# LVDS.net
KiCad netlist of a schematic drawn in Altium Designer
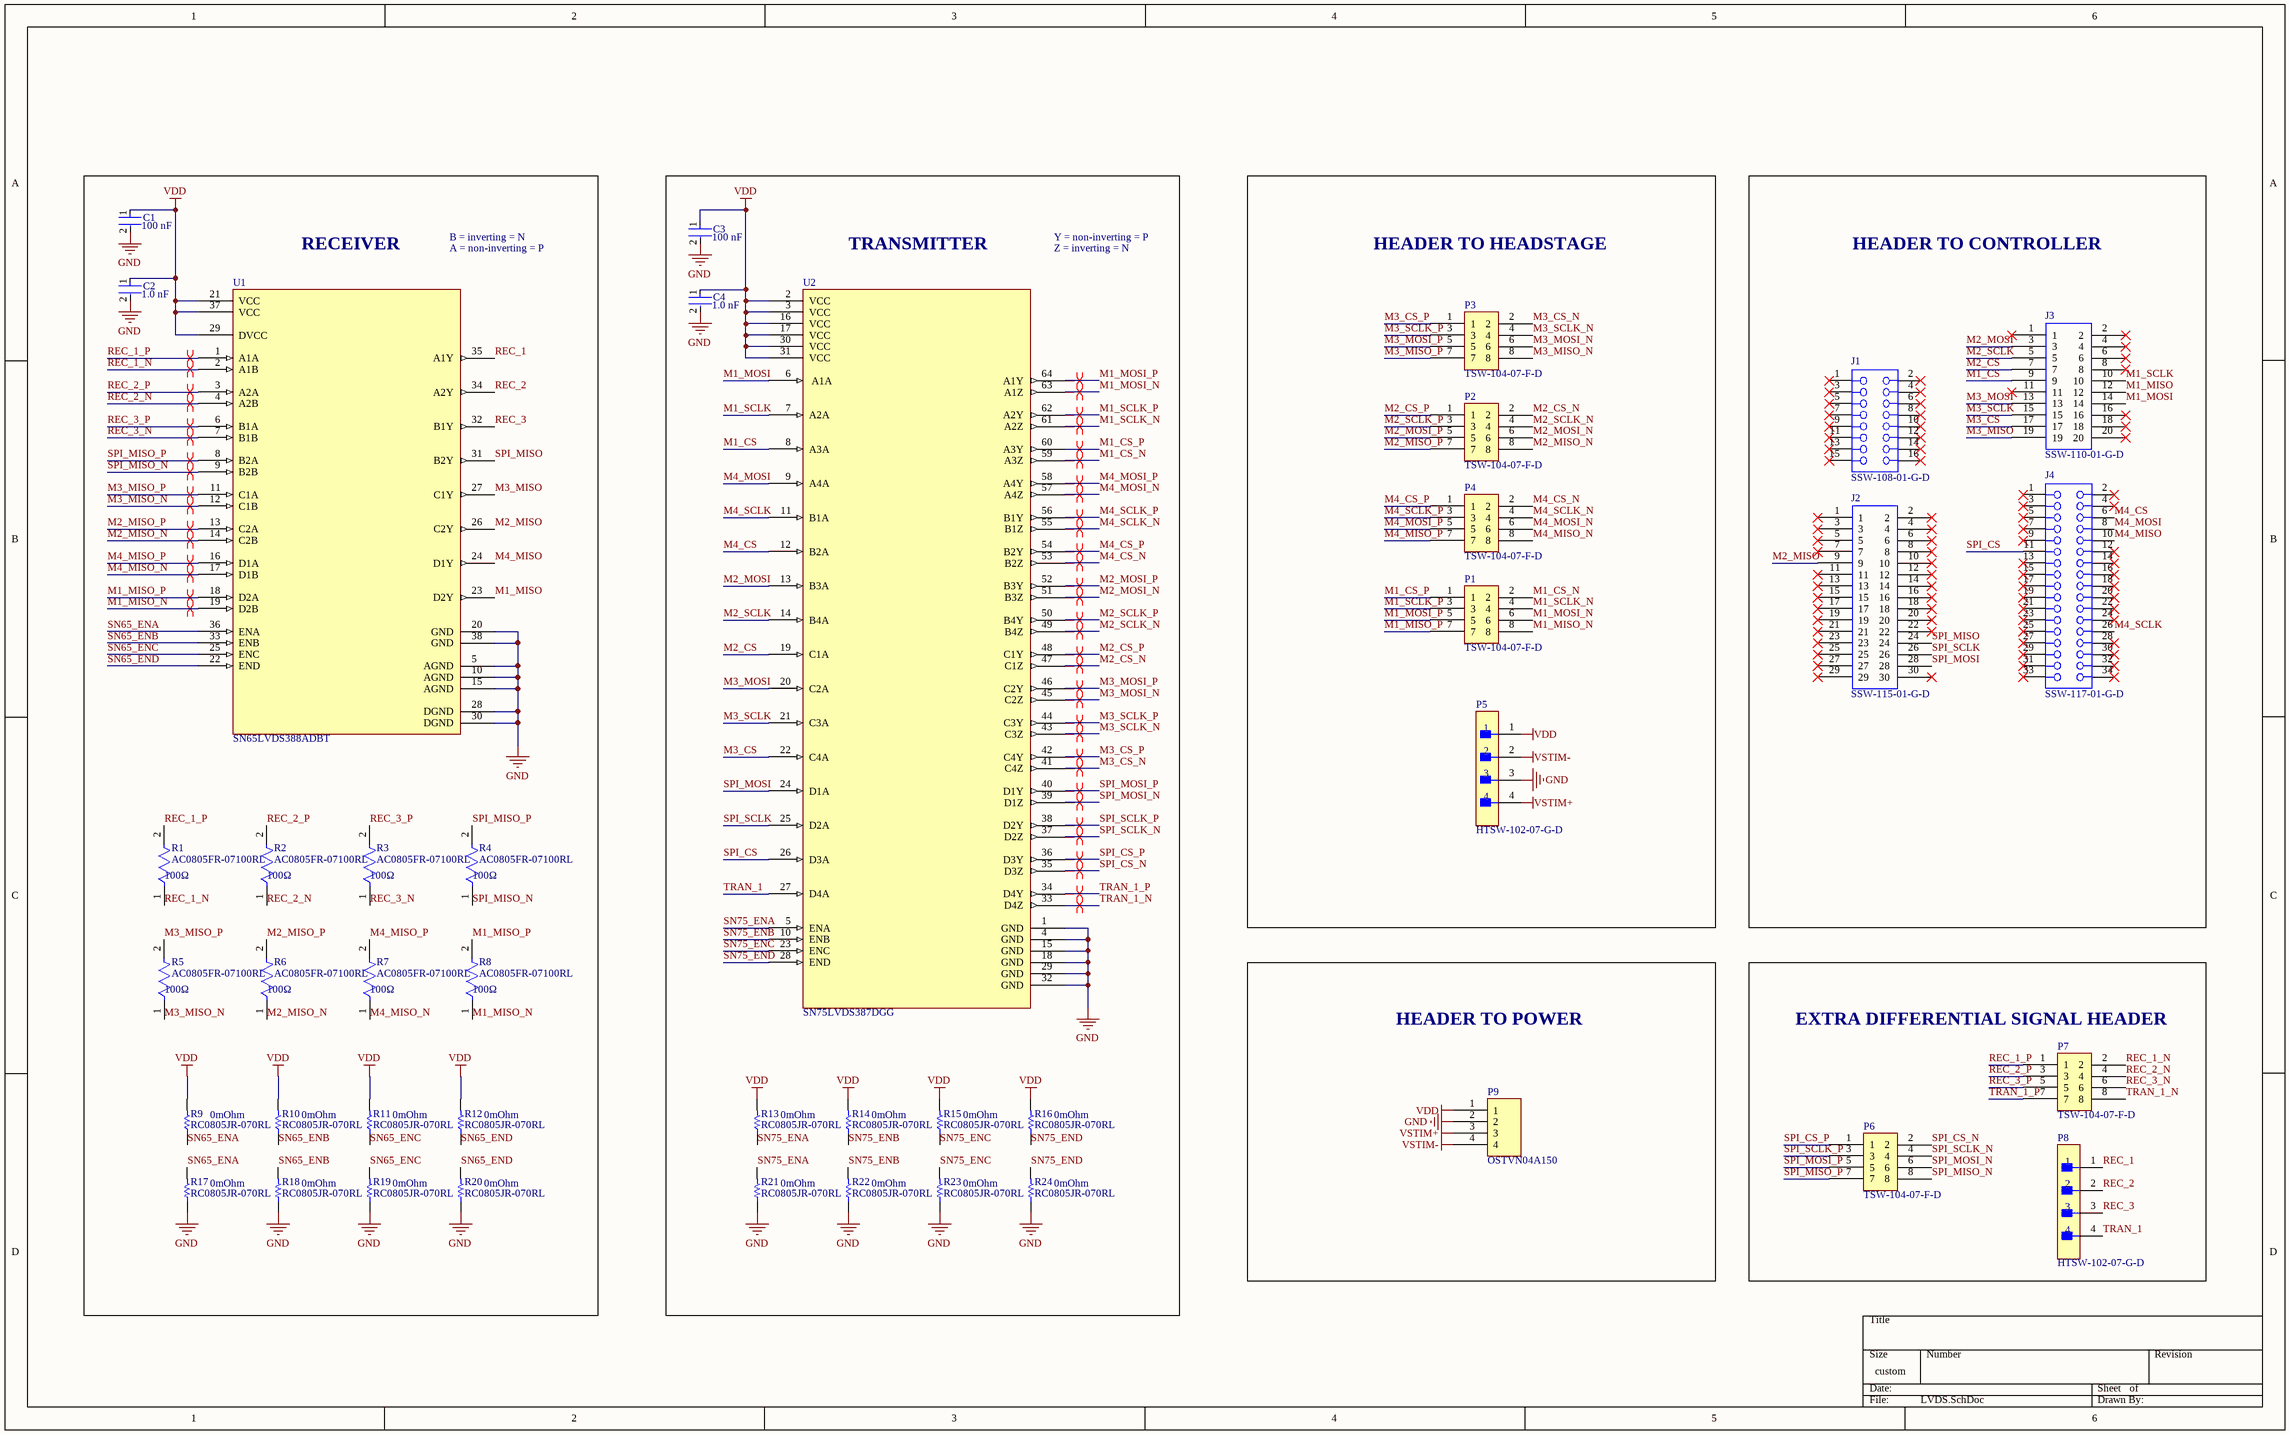
[diagram p0: LVDS.SchDoc]

(export (version "E")
  (design (tool "Eeschema 10.0.6"))
  (components
    (comp (ref "C1")
      (value "CC0805MRX7R9BB104")
      (footprint "FP-CC0805-0_85-MFG")
      (description "CAP CER 0.1UF 50V X7R 0805")
      (fields
        (field (name "TOLERANCE") "0.2")
        (field (name "OCTOPART") "https://octopart.com/cc0805mrx7r9bb104-yageo-30261726")
        (field (name "CAPACITANCE") "100 nF")
      )
      (libsource (lib "Altium Content Vault") (part "11868f565c42a9108669ba33697ecf6"))
    )
    (comp (ref "C2")
      (value "CC0805KRX7R9BB102")
      (footprint "FP-CC0805-0_85-MFG")
      (description "CAP CER 1000PF 50V X7R 0805")
      (fields
        (field (name "MANUFACTURER") "Yageo")
        (field (name "OCTOPART") "https://octopart.com/cc0805krx7r9bb102-yageo-39467744")
        (field (name "CAPACITANCE") "1.0 nF")
      )
      (libsource (lib "Altium Content Vault") (part "11868f565c42a9108669ba33697ecf6"))
    )
    (comp (ref "C3")
      (value "CC0805MRX7R9BB104")
      (footprint "FP-CC0805-0_85-MFG")
      (description "CAP CER 0.1UF 50V X7R 0805")
      (fields
        (field (name "TOLERANCE") "0.2")
        (field (name "OCTOPART") "https://octopart.com/cc0805mrx7r9bb104-yageo-30261726")
        (field (name "CAPACITANCE") "100 nF")
      )
      (libsource (lib "Altium Content Vault") (part "11868f565c42a9108669ba33697ecf6"))
    )
    (comp (ref "C4")
      (value "CC0805KRX7R9BB102")
      (footprint "FP-CC0805-0_85-MFG")
      (description "CAP CER 1000PF 50V X7R 0805")
      (fields
        (field (name "MANUFACTURER") "Yageo")
        (field (name "OCTOPART") "https://octopart.com/cc0805krx7r9bb102-yageo-39467744")
        (field (name "CAPACITANCE") "1.0 nF")
      )
      (libsource (lib "Altium Content Vault") (part "11868f565c42a9108669ba33697ecf6"))
    )
    (comp (ref "J1")
      (value "SSW-108-01-G-D")
      (footprint "SMTC-SSW-108-01-X-D")
      (description "SQ Post Socket, Through-hole, Vertical, -55 to 125 degC, 2.54mm Pitch, 16-Pin, Female, RoHS")
      (fields (field (name "MANUFACTURER") "Samtec"))
      (libsource (lib "Altium Content Vault") (part "SMTC-SSW-108-X-X-D-X"))
    )
    (comp (ref "J2")
      (value "SSW-115-01-G-D")
      (footprint "SAMTEC_SSW-115-01-G-D")
      (fields (field (name "MANUFACTURER") "Samtec"))
      (libsource (lib "LVDS") (part "SSW-115-01-G-D"))
    )
    (comp (ref "J3")
      (value "SSW-110-01-G-D")
      (footprint "SAMTEC_SSW-110-01-G-D")
      (fields (field (name "MANUFACTURER") "Samtec"))
      (libsource (lib "LVDS") (part "SSW-110-01-G-D"))
    )
    (comp (ref "J4")
      (value "SSW-117-01-G-D")
      (footprint "SMTC-SSW-117-01-X-D")
      (description "SQ Post Socket, Through-hole, Vertical, -55 to 125 degC, 2.54 mm Pitch, 34-Pin, Female, RoHS")
      (fields (field (name "MANUFACTURER") "Samtec"))
      (libsource (lib "Altium Content Vault") (part "SMTC-SSW-117-01-X-D"))
    )
    (comp (ref "P1")
      (value "TSW-104-07-F-D")
      (footprint "SAMTEC_TSW-104-07-F-D")
      (fields (field (name "MANUFACTURER") "Samtec"))
      (libsource (lib "LVDS") (part "TSW-104-07-F-D"))
    )
    (comp (ref "P2")
      (value "TSW-104-07-F-D")
      (footprint "SAMTEC_TSW-104-07-F-D")
      (fields (field (name "MANUFACTURER") "Samtec"))
      (libsource (lib "LVDS") (part "TSW-104-07-F-D"))
    )
    (comp (ref "P3")
      (value "TSW-104-07-F-D")
      (footprint "SAMTEC_TSW-104-07-F-D")
      (fields (field (name "MANUFACTURER") "Samtec"))
      (libsource (lib "LVDS") (part "TSW-104-07-F-D"))
    )
    (comp (ref "P4")
      (value "TSW-104-07-F-D")
      (footprint "SAMTEC_TSW-104-07-F-D")
      (fields (field (name "MANUFACTURER") "Samtec"))
      (libsource (lib "LVDS") (part "TSW-104-07-F-D"))
    )
    (comp (ref "P5")
      (value "HTSW-102-07-G-D")
      (footprint "FP-HTSW-102-07-G-D-MFG")
      (description "CONN HEADER VERT 4POS 2.54MM")
      (fields
        (field (name "MANUFACTURER") "Samtec")
        (field (name "OCTOPART") "https://octopart.com/htsw-102-07-g-d-samtec-10531767")
      )
      (libsource (lib "Altium Content Vault") (part "299a8cea1bdcbc3624fe62c390fa72c"))
    )
    (comp (ref "P6")
      (value "TSW-104-07-F-D")
      (footprint "SAMTEC_TSW-104-07-F-D")
      (fields (field (name "MANUFACTURER") "Samtec"))
      (libsource (lib "LVDS") (part "TSW-104-07-F-D"))
    )
    (comp (ref "P7")
      (value "TSW-104-07-F-D")
      (footprint "SAMTEC_TSW-104-07-F-D")
      (fields (field (name "MANUFACTURER") "Samtec"))
      (libsource (lib "LVDS") (part "TSW-104-07-F-D"))
    )
    (comp (ref "P8")
      (value "HTSW-102-07-G-D")
      (footprint "FP-HTSW-102-07-G-D-MFG")
      (description "CONN HEADER VERT 4POS 2.54MM")
      (fields
        (field (name "MANUFACTURER") "Samtec")
        (field (name "OCTOPART") "https://octopart.com/htsw-102-07-g-d-samtec-10531767")
      )
      (libsource (lib "Altium Content Vault") (part "299a8cea1bdcbc3624fe62c390fa72c"))
    )
    (comp (ref "P9")
      (value "OSTVN04A150")
      (footprint "OSTVN04A150")
      (description "Barrier Strip Terminal Block, 6A, 1 Row(s), 1 Deck(s)")
      (fields (field (name "MANUFACTURER") "On-Shore Technology") (field (name "SAFETY APPROVAL") "UL,CUL"))
      (libsource (lib "LVDS") (part "OSTVN04A150"))
    )
    (comp (ref "R1")
      (value "AC0805FR-07100RL")
      (footprint "FP-AC0805-MFG")
      (description "Res Thick Film 0805 100 Ohm 1% 1/8W ±100ppm/°C Molded SMD Paper T/R")
      (fields
        (field (name "TOLERANCE") "0.01")
        (field (name "OCTOPART") "https://octopart.com/ac0805fr-07100rl-yageo-24517276")
        (field (name "RESISTANCE") "100Ω")
      )
      (libsource (lib "Altium Content Vault") (part "1029c3af85768c4190bb7ad29bc67b5"))
    )
    (comp (ref "R2")
      (value "AC0805FR-07100RL")
      (footprint "FP-AC0805-MFG")
      (description "Res Thick Film 0805 100 Ohm 1% 1/8W ±100ppm/°C Molded SMD Paper T/R")
      (fields
        (field (name "TOLERANCE") "0.01")
        (field (name "OCTOPART") "https://octopart.com/ac0805fr-07100rl-yageo-24517276")
        (field (name "RESISTANCE") "100Ω")
      )
      (libsource (lib "Altium Content Vault") (part "1029c3af85768c4190bb7ad29bc67b5"))
    )
    (comp (ref "R3")
      (value "AC0805FR-07100RL")
      (footprint "FP-AC0805-MFG")
      (description "Res Thick Film 0805 100 Ohm 1% 1/8W ±100ppm/°C Molded SMD Paper T/R")
      (fields
        (field (name "TOLERANCE") "0.01")
        (field (name "OCTOPART") "https://octopart.com/ac0805fr-07100rl-yageo-24517276")
        (field (name "RESISTANCE") "100Ω")
      )
      (libsource (lib "Altium Content Vault") (part "1029c3af85768c4190bb7ad29bc67b5"))
    )
    (comp (ref "R4")
      (value "AC0805FR-07100RL")
      (footprint "FP-AC0805-MFG")
      (description "Res Thick Film 0805 100 Ohm 1% 1/8W ±100ppm/°C Molded SMD Paper T/R")
      (fields
        (field (name "TOLERANCE") "0.01")
        (field (name "OCTOPART") "https://octopart.com/ac0805fr-07100rl-yageo-24517276")
        (field (name "RESISTANCE") "100Ω")
      )
      (libsource (lib "Altium Content Vault") (part "1029c3af85768c4190bb7ad29bc67b5"))
    )
    (comp (ref "R5")
      (value "AC0805FR-07100RL")
      (footprint "FP-AC0805-MFG")
      (description "Res Thick Film 0805 100 Ohm 1% 1/8W ±100ppm/°C Molded SMD Paper T/R")
      (fields
        (field (name "TOLERANCE") "0.01")
        (field (name "OCTOPART") "https://octopart.com/ac0805fr-07100rl-yageo-24517276")
        (field (name "RESISTANCE") "100Ω")
      )
      (libsource (lib "Altium Content Vault") (part "1029c3af85768c4190bb7ad29bc67b5"))
    )
    (comp (ref "R6")
      (value "AC0805FR-07100RL")
      (footprint "FP-AC0805-MFG")
      (description "Res Thick Film 0805 100 Ohm 1% 1/8W ±100ppm/°C Molded SMD Paper T/R")
      (fields
        (field (name "TOLERANCE") "0.01")
        (field (name "OCTOPART") "https://octopart.com/ac0805fr-07100rl-yageo-24517276")
        (field (name "RESISTANCE") "100Ω")
      )
      (libsource (lib "Altium Content Vault") (part "1029c3af85768c4190bb7ad29bc67b5"))
    )
    (comp (ref "R7")
      (value "AC0805FR-07100RL")
      (footprint "FP-AC0805-MFG")
      (description "Res Thick Film 0805 100 Ohm 1% 1/8W ±100ppm/°C Molded SMD Paper T/R")
      (fields
        (field (name "TOLERANCE") "0.01")
        (field (name "OCTOPART") "https://octopart.com/ac0805fr-07100rl-yageo-24517276")
        (field (name "RESISTANCE") "100Ω")
      )
      (libsource (lib "Altium Content Vault") (part "1029c3af85768c4190bb7ad29bc67b5"))
    )
    (comp (ref "R8")
      (value "AC0805FR-07100RL")
      (footprint "FP-AC0805-MFG")
      (description "Res Thick Film 0805 100 Ohm 1% 1/8W ±100ppm/°C Molded SMD Paper T/R")
      (fields
        (field (name "TOLERANCE") "0.01")
        (field (name "OCTOPART") "https://octopart.com/ac0805fr-07100rl-yageo-24517276")
        (field (name "RESISTANCE") "100Ω")
      )
      (libsource (lib "Altium Content Vault") (part "1029c3af85768c4190bb7ad29bc67b5"))
    )
    (comp (ref "R9")
      (value "RC0805JR-070RL")
      (footprint "RESC2013X60X35ML10T20")
      (fields
        (field (name "RESISTANCE") "0mOhm")
        (field (name "TOLERANCE") "5%")
        (field (name "MANUFACTURER") "Yageo")
      )
      (libsource (lib "Altium Content Vault") (part "RES-2"))
    )
    (comp (ref "R10")
      (value "RC0805JR-070RL")
      (footprint "RESC2013X60X35ML10T20")
      (fields
        (field (name "RESISTANCE") "0mOhm")
        (field (name "TOLERANCE") "5%")
        (field (name "MANUFACTURER") "Yageo")
      )
      (libsource (lib "Altium Content Vault") (part "RES-2"))
    )
    (comp (ref "R11")
      (value "RC0805JR-070RL")
      (footprint "RESC2013X60X35ML10T20")
      (fields
        (field (name "RESISTANCE") "0mOhm")
        (field (name "TOLERANCE") "5%")
        (field (name "MANUFACTURER") "Yageo")
      )
      (libsource (lib "Altium Content Vault") (part "RES-2"))
    )
    (comp (ref "R12")
      (value "RC0805JR-070RL")
      (footprint "RESC2013X60X35ML10T20")
      (fields
        (field (name "RESISTANCE") "0mOhm")
        (field (name "TOLERANCE") "5%")
        (field (name "MANUFACTURER") "Yageo")
      )
      (libsource (lib "Altium Content Vault") (part "RES-2"))
    )
    (comp (ref "R13")
      (value "RC0805JR-070RL")
      (footprint "RESC2013X60X35ML10T20")
      (fields
        (field (name "RESISTANCE") "0mOhm")
        (field (name "TOLERANCE") "5%")
        (field (name "MANUFACTURER") "Yageo")
      )
      (libsource (lib "Altium Content Vault") (part "RES-2"))
    )
    (comp (ref "R14")
      (value "RC0805JR-070RL")
      (footprint "RESC2013X60X35ML10T20")
      (fields
        (field (name "RESISTANCE") "0mOhm")
        (field (name "TOLERANCE") "5%")
        (field (name "MANUFACTURER") "Yageo")
      )
      (libsource (lib "Altium Content Vault") (part "RES-2"))
    )
    (comp (ref "R15")
      (value "RC0805JR-070RL")
      (footprint "RESC2013X60X35ML10T20")
      (fields
        (field (name "RESISTANCE") "0mOhm")
        (field (name "TOLERANCE") "5%")
        (field (name "MANUFACTURER") "Yageo")
      )
      (libsource (lib "Altium Content Vault") (part "RES-2"))
    )
    (comp (ref "R16")
      (value "RC0805JR-070RL")
      (footprint "RESC2013X60X35ML10T20")
      (fields
        (field (name "RESISTANCE") "0mOhm")
        (field (name "TOLERANCE") "5%")
        (field (name "MANUFACTURER") "Yageo")
      )
      (libsource (lib "Altium Content Vault") (part "RES-2"))
    )
    (comp (ref "R17")
      (value "RC0805JR-070RL")
      (footprint "RESC2013X60X35ML10T20")
      (fields
        (field (name "RESISTANCE") "0mOhm")
        (field (name "TOLERANCE") "5%")
        (field (name "MANUFACTURER") "Yageo")
      )
      (libsource (lib "Altium Content Vault") (part "RES-2"))
    )
    (comp (ref "R18")
      (value "RC0805JR-070RL")
      (footprint "RESC2013X60X35ML10T20")
      (fields
        (field (name "RESISTANCE") "0mOhm")
        (field (name "TOLERANCE") "5%")
        (field (name "MANUFACTURER") "Yageo")
      )
      (libsource (lib "Altium Content Vault") (part "RES-2"))
    )
    (comp (ref "R19")
      (value "RC0805JR-070RL")
      (footprint "RESC2013X60X35ML10T20")
      (fields
        (field (name "RESISTANCE") "0mOhm")
        (field (name "TOLERANCE") "5%")
        (field (name "MANUFACTURER") "Yageo")
      )
      (libsource (lib "Altium Content Vault") (part "RES-2"))
    )
    (comp (ref "R20")
      (value "RC0805JR-070RL")
      (footprint "RESC2013X60X35ML10T20")
      (fields
        (field (name "RESISTANCE") "0mOhm")
        (field (name "TOLERANCE") "5%")
        (field (name "MANUFACTURER") "Yageo")
      )
      (libsource (lib "Altium Content Vault") (part "RES-2"))
    )
    (comp (ref "R21")
      (value "RC0805JR-070RL")
      (footprint "RESC2013X60X35ML10T20")
      (fields
        (field (name "RESISTANCE") "0mOhm")
        (field (name "TOLERANCE") "5%")
        (field (name "MANUFACTURER") "Yageo")
      )
      (libsource (lib "Altium Content Vault") (part "RES-2"))
    )
    (comp (ref "R22")
      (value "RC0805JR-070RL")
      (footprint "RESC2013X60X35ML10T20")
      (fields
        (field (name "RESISTANCE") "0mOhm")
        (field (name "TOLERANCE") "5%")
        (field (name "MANUFACTURER") "Yageo")
      )
      (libsource (lib "Altium Content Vault") (part "RES-2"))
    )
    (comp (ref "R23")
      (value "RC0805JR-070RL")
      (footprint "RESC2013X60X35ML10T20")
      (fields
        (field (name "RESISTANCE") "0mOhm")
        (field (name "TOLERANCE") "5%")
        (field (name "MANUFACTURER") "Yageo")
      )
      (libsource (lib "Altium Content Vault") (part "RES-2"))
    )
    (comp (ref "R24")
      (value "RC0805JR-070RL")
      (footprint "RESC2013X60X35ML10T20")
      (fields
        (field (name "RESISTANCE") "0mOhm")
        (field (name "TOLERANCE") "5%")
        (field (name "MANUFACTURER") "Yageo")
      )
      (libsource (lib "Altium Content Vault") (part "RES-2"))
    )
    (comp (ref "U1")
      (value "SN65LVDS388ADBT")
      (footprint "DBT0038A_N")
      (description "Line Receiver, 8 Func, 8 Rcvr, CMOS, PDSO38")
      (fields (field (name "MANUFACTURER") "Texas Instruments"))
      (libsource (lib "LVDS") (part "SN65LVDS388ADBT"))
    )
    (comp (ref "U2")
      (value "SN75LVDS387DGG")
      (footprint "DGG64")
      (description "Line Driver, 16 Func, 16 Driver, CMOS, PDSO64")
      (fields (field (name "MANUFACTURER") "Texas Instruments"))
      (libsource (lib "LVDS") (part "SN75LVDS387DGG"))
    )
  )
  (nets
    (net (code "1") (name "/M1_CS") (class "Default")
      (node (ref "J3") (pin "9") (pinfunction "9_9") (pintype "passive"))
      (node (ref "U2") (pin "8") (pinfunction "A3A_8") (pintype "input"))
    )
    (net (code "2") (name "/M1_CS_N") (class "Default")
      (node (ref "P1") (pin "2") (pinfunction "2_2") (pintype "passive"))
      (node (ref "U2") (pin "59") (pinfunction "A3Z_59") (pintype "output"))
    )
    (net (code "3") (name "/M1_CS_P") (class "Default")
      (node (ref "P1") (pin "1") (pinfunction "1_1") (pintype "passive"))
      (node (ref "U2") (pin "60") (pinfunction "A3Y_60") (pintype "output"))
    )
    (net (code "4") (name "/M1_MISO") (class "Default")
      (node (ref "J3") (pin "12") (pinfunction "12_12") (pintype "passive"))
      (node (ref "U1") (pin "23") (pinfunction "D2Y_23") (pintype "output"))
    )
    (net (code "5") (name "/M1_MISO_N") (class "Default")
      (node (ref "P1") (pin "8") (pinfunction "8_8") (pintype "passive"))
      (node (ref "R8") (pin "1") (pinfunction "1_1") (pintype "passive"))
      (node (ref "U1") (pin "19") (pinfunction "D2B_19") (pintype "input"))
    )
    (net (code "6") (name "/M1_MISO_P") (class "Default")
      (node (ref "P1") (pin "7") (pinfunction "7_7") (pintype "passive"))
      (node (ref "R8") (pin "2") (pinfunction "2_2") (pintype "passive"))
      (node (ref "U1") (pin "18") (pinfunction "D2A_18") (pintype "input"))
    )
    (net (code "7") (name "/M1_MOSI") (class "Default")
      (node (ref "J3") (pin "14") (pinfunction "14_14") (pintype "passive"))
      (node (ref "U2") (pin "6") (pinfunction "_A1A_6") (pintype "input"))
    )
    (net (code "8") (name "/M1_MOSI_N") (class "Default")
      (node (ref "P1") (pin "6") (pinfunction "6_6") (pintype "passive"))
      (node (ref "U2") (pin "63") (pinfunction "A1Z_63") (pintype "output"))
    )
    (net (code "9") (name "/M1_MOSI_P") (class "Default")
      (node (ref "P1") (pin "5") (pinfunction "5_5") (pintype "passive"))
      (node (ref "U2") (pin "64") (pinfunction "A1Y_64") (pintype "output"))
    )
    (net (code "10") (name "/M1_SCLK") (class "Default")
      (node (ref "J3") (pin "10") (pinfunction "10_10") (pintype "passive"))
      (node (ref "U2") (pin "7") (pinfunction "A2A_7") (pintype "input"))
    )
    (net (code "11") (name "/M1_SCLK_N") (class "Default")
      (node (ref "P1") (pin "4") (pinfunction "4_4") (pintype "passive"))
      (node (ref "U2") (pin "61") (pinfunction "A2Z_61") (pintype "output"))
    )
    (net (code "12") (name "/M1_SCLK_P") (class "Default")
      (node (ref "P1") (pin "3") (pinfunction "3_3") (pintype "passive"))
      (node (ref "U2") (pin "62") (pinfunction "A2Y_62") (pintype "output"))
    )
    (net (code "13") (name "/M2_CS") (class "Default")
      (node (ref "J3") (pin "7") (pinfunction "7_7") (pintype "passive"))
      (node (ref "U2") (pin "19") (pinfunction "C1A_19") (pintype "input"))
    )
    (net (code "14") (name "/M2_CS_N") (class "Default")
      (node (ref "P2") (pin "2") (pinfunction "2_2") (pintype "passive"))
      (node (ref "U2") (pin "47") (pinfunction "C1Z_47") (pintype "output"))
    )
    (net (code "15") (name "/M2_CS_P") (class "Default")
      (node (ref "P2") (pin "1") (pinfunction "1_1") (pintype "passive"))
      (node (ref "U2") (pin "48") (pinfunction "C1Y_48") (pintype "output"))
    )
    (net (code "16") (name "/M2_MISO") (class "Default")
      (node (ref "J2") (pin "9") (pinfunction "9_9") (pintype "passive"))
      (node (ref "U1") (pin "26") (pinfunction "C2Y_26") (pintype "output"))
    )
    (net (code "17") (name "/M2_MISO_N") (class "Default")
      (node (ref "P2") (pin "8") (pinfunction "8_8") (pintype "passive"))
      (node (ref "R6") (pin "1") (pinfunction "1_1") (pintype "passive"))
      (node (ref "U1") (pin "14") (pinfunction "C2B_14") (pintype "input"))
    )
    (net (code "18") (name "/M2_MISO_P") (class "Default")
      (node (ref "P2") (pin "7") (pinfunction "7_7") (pintype "passive"))
      (node (ref "R6") (pin "2") (pinfunction "2_2") (pintype "passive"))
      (node (ref "U1") (pin "13") (pinfunction "C2A_13") (pintype "input"))
    )
    (net (code "19") (name "/M2_MOSI") (class "Default")
      (node (ref "J3") (pin "3") (pinfunction "3_3") (pintype "passive"))
      (node (ref "U2") (pin "13") (pinfunction "B3A_13") (pintype "input"))
    )
    (net (code "20") (name "/M2_MOSI_N") (class "Default")
      (node (ref "P2") (pin "6") (pinfunction "6_6") (pintype "passive"))
      (node (ref "U2") (pin "51") (pinfunction "B3Z_51") (pintype "output"))
    )
    (net (code "21") (name "/M2_MOSI_P") (class "Default")
      (node (ref "P2") (pin "5") (pinfunction "5_5") (pintype "passive"))
      (node (ref "U2") (pin "52") (pinfunction "B3Y_52") (pintype "output"))
    )
    (net (code "22") (name "/M2_SCLK") (class "Default")
      (node (ref "J3") (pin "5") (pinfunction "5_5") (pintype "passive"))
      (node (ref "U2") (pin "14") (pinfunction "B4A_14") (pintype "input"))
    )
    (net (code "23") (name "/M2_SCLK_N") (class "Default")
      (node (ref "P2") (pin "4") (pinfunction "4_4") (pintype "passive"))
      (node (ref "U2") (pin "49") (pinfunction "B4Z_49") (pintype "output"))
    )
    (net (code "24") (name "/M2_SCLK_P") (class "Default")
      (node (ref "P2") (pin "3") (pinfunction "3_3") (pintype "passive"))
      (node (ref "U2") (pin "50") (pinfunction "B4Y_50") (pintype "output"))
    )
    (net (code "25") (name "/M3_CS") (class "Default")
      (node (ref "J3") (pin "17") (pinfunction "17_17") (pintype "passive"))
      (node (ref "U2") (pin "22") (pinfunction "C4A_22") (pintype "input"))
    )
    (net (code "26") (name "/M3_CS_N") (class "Default")
      (node (ref "P3") (pin "2") (pinfunction "2_2") (pintype "passive"))
      (node (ref "U2") (pin "41") (pinfunction "C4Z_41") (pintype "output"))
    )
    (net (code "27") (name "/M3_CS_P") (class "Default")
      (node (ref "P3") (pin "1") (pinfunction "1_1") (pintype "passive"))
      (node (ref "U2") (pin "42") (pinfunction "C4Y_42") (pintype "output"))
    )
    (net (code "28") (name "/M3_MISO") (class "Default")
      (node (ref "J3") (pin "19") (pinfunction "19_19") (pintype "passive"))
      (node (ref "U1") (pin "27") (pinfunction "C1Y_27") (pintype "output"))
    )
    (net (code "29") (name "/M3_MISO_N") (class "Default")
      (node (ref "P3") (pin "8") (pinfunction "8_8") (pintype "passive"))
      (node (ref "R5") (pin "1") (pinfunction "1_1") (pintype "passive"))
      (node (ref "U1") (pin "12") (pinfunction "C1B_12") (pintype "input"))
    )
    (net (code "30") (name "/M3_MISO_P") (class "Default")
      (node (ref "P3") (pin "7") (pinfunction "7_7") (pintype "passive"))
      (node (ref "R5") (pin "2") (pinfunction "2_2") (pintype "passive"))
      (node (ref "U1") (pin "11") (pinfunction "C1A_11") (pintype "input"))
    )
    (net (code "31") (name "/M3_MOSI") (class "Default")
      (node (ref "J3") (pin "13") (pinfunction "13_13") (pintype "passive"))
      (node (ref "U2") (pin "20") (pinfunction "C2A_20") (pintype "input"))
    )
    (net (code "32") (name "/M3_MOSI_N") (class "Default")
      (node (ref "P3") (pin "6") (pinfunction "6_6") (pintype "passive"))
      (node (ref "U2") (pin "45") (pinfunction "C2Z_45") (pintype "output"))
    )
    (net (code "33") (name "/M3_MOSI_P") (class "Default")
      (node (ref "P3") (pin "5") (pinfunction "5_5") (pintype "passive"))
      (node (ref "U2") (pin "46") (pinfunction "C2Y_46") (pintype "output"))
    )
    (net (code "34") (name "/M3_SCLK") (class "Default")
      (node (ref "J3") (pin "15") (pinfunction "15_15") (pintype "passive"))
      (node (ref "U2") (pin "21") (pinfunction "C3A_21") (pintype "input"))
    )
    (net (code "35") (name "/M3_SCLK_N") (class "Default")
      (node (ref "P3") (pin "4") (pinfunction "4_4") (pintype "passive"))
      (node (ref "U2") (pin "43") (pinfunction "C3Z_43") (pintype "output"))
    )
    (net (code "36") (name "/M3_SCLK_P") (class "Default")
      (node (ref "P3") (pin "3") (pinfunction "3_3") (pintype "passive"))
      (node (ref "U2") (pin "44") (pinfunction "C3Y_44") (pintype "output"))
    )
    (net (code "37") (name "/M4_CS") (class "Default")
      (node (ref "J4") (pin "6") (pinfunction "6_6") (pintype "passive"))
      (node (ref "U2") (pin "12") (pinfunction "B2A_12") (pintype "input"))
    )
    (net (code "38") (name "/M4_CS_N") (class "Default")
      (node (ref "P4") (pin "2") (pinfunction "2_2") (pintype "passive"))
      (node (ref "U2") (pin "53") (pinfunction "B2Z_53") (pintype "output"))
    )
    (net (code "39") (name "/M4_CS_P") (class "Default")
      (node (ref "P4") (pin "1") (pinfunction "1_1") (pintype "passive"))
      (node (ref "U2") (pin "54") (pinfunction "B2Y_54") (pintype "output"))
    )
    (net (code "40") (name "/M4_MISO") (class "Default")
      (node (ref "J4") (pin "10") (pinfunction "10_10") (pintype "passive"))
      (node (ref "U1") (pin "24") (pinfunction "D1Y_24") (pintype "output"))
    )
    (net (code "41") (name "/M4_MISO_N") (class "Default")
      (node (ref "P4") (pin "8") (pinfunction "8_8") (pintype "passive"))
      (node (ref "R7") (pin "1") (pinfunction "1_1") (pintype "passive"))
      (node (ref "U1") (pin "17") (pinfunction "D1B_17") (pintype "input"))
    )
    (net (code "42") (name "/M4_MISO_P") (class "Default")
      (node (ref "P4") (pin "7") (pinfunction "7_7") (pintype "passive"))
      (node (ref "R7") (pin "2") (pinfunction "2_2") (pintype "passive"))
      (node (ref "U1") (pin "16") (pinfunction "D1A_16") (pintype "input"))
    )
    (net (code "43") (name "/M4_MOSI") (class "Default")
      (node (ref "J4") (pin "8") (pinfunction "8_8") (pintype "passive"))
      (node (ref "U2") (pin "9") (pinfunction "A4A_9") (pintype "input"))
    )
    (net (code "44") (name "/M4_MOSI_N") (class "Default")
      (node (ref "P4") (pin "6") (pinfunction "6_6") (pintype "passive"))
      (node (ref "U2") (pin "57") (pinfunction "A4Z_57") (pintype "output"))
    )
    (net (code "45") (name "/M4_MOSI_P") (class "Default")
      (node (ref "P4") (pin "5") (pinfunction "5_5") (pintype "passive"))
      (node (ref "U2") (pin "58") (pinfunction "A4Y_58") (pintype "output"))
    )
    (net (code "46") (name "/M4_SCLK") (class "Default")
      (node (ref "J4") (pin "26") (pinfunction "26_26") (pintype "passive"))
      (node (ref "U2") (pin "11") (pinfunction "B1A_11") (pintype "input"))
    )
    (net (code "47") (name "/M4_SCLK_N") (class "Default")
      (node (ref "P4") (pin "4") (pinfunction "4_4") (pintype "passive"))
      (node (ref "U2") (pin "55") (pinfunction "B1Z_55") (pintype "output"))
    )
    (net (code "48") (name "/M4_SCLK_P") (class "Default")
      (node (ref "P4") (pin "3") (pinfunction "3_3") (pintype "passive"))
      (node (ref "U2") (pin "56") (pinfunction "B1Y_56") (pintype "output"))
    )
    (net (code "49") (name "/REC_1") (class "Default")
      (node (ref "P8") (pin "1") (pinfunction "1_1") (pintype "passive"))
      (node (ref "U1") (pin "35") (pinfunction "A1Y_35") (pintype "output"))
    )
    (net (code "50") (name "/REC_1_N") (class "Default")
      (node (ref "P7") (pin "2") (pinfunction "2_2") (pintype "passive"))
      (node (ref "R1") (pin "1") (pinfunction "1_1") (pintype "passive"))
      (node (ref "U1") (pin "2") (pinfunction "A1B_2") (pintype "input"))
    )
    (net (code "51") (name "/REC_1_P") (class "Default")
      (node (ref "P7") (pin "1") (pinfunction "1_1") (pintype "passive"))
      (node (ref "R1") (pin "2") (pinfunction "2_2") (pintype "passive"))
      (node (ref "U1") (pin "1") (pinfunction "A1A_1") (pintype "input"))
    )
    (net (code "52") (name "/REC_2") (class "Default")
      (node (ref "P8") (pin "2") (pinfunction "2_2") (pintype "passive"))
      (node (ref "U1") (pin "34") (pinfunction "A2Y_34") (pintype "output"))
    )
    (net (code "53") (name "/REC_2_N") (class "Default")
      (node (ref "P7") (pin "4") (pinfunction "4_4") (pintype "passive"))
      (node (ref "R2") (pin "1") (pinfunction "1_1") (pintype "passive"))
      (node (ref "U1") (pin "4") (pinfunction "A2B_4") (pintype "input"))
    )
    (net (code "54") (name "/REC_2_P") (class "Default")
      (node (ref "P7") (pin "3") (pinfunction "3_3") (pintype "passive"))
      (node (ref "R2") (pin "2") (pinfunction "2_2") (pintype "passive"))
      (node (ref "U1") (pin "3") (pinfunction "A2A_3") (pintype "input"))
    )
    (net (code "55") (name "/REC_3") (class "Default")
      (node (ref "P8") (pin "3") (pinfunction "3_3") (pintype "passive"))
      (node (ref "U1") (pin "32") (pinfunction "B1Y_32") (pintype "output"))
    )
    (net (code "56") (name "/REC_3_N") (class "Default")
      (node (ref "P7") (pin "6") (pinfunction "6_6") (pintype "passive"))
      (node (ref "R3") (pin "1") (pinfunction "1_1") (pintype "passive"))
      (node (ref "U1") (pin "7") (pinfunction "B1B_7") (pintype "input"))
    )
    (net (code "57") (name "/REC_3_P") (class "Default")
      (node (ref "P7") (pin "5") (pinfunction "5_5") (pintype "passive"))
      (node (ref "R3") (pin "2") (pinfunction "2_2") (pintype "passive"))
      (node (ref "U1") (pin "6") (pinfunction "B1A_6") (pintype "input"))
    )
    (net (code "58") (name "/SN65_ENA") (class "Default")
      (node (ref "R17") (pin "2") (pinfunction "2_2") (pintype "passive"))
      (node (ref "R9") (pin "1") (pinfunction "1_1") (pintype "passive"))
      (node (ref "U1") (pin "36") (pinfunction "ENA_36") (pintype "input"))
    )
    (net (code "59") (name "/SN65_ENB") (class "Default")
      (node (ref "R10") (pin "1") (pinfunction "1_1") (pintype "passive"))
      (node (ref "R18") (pin "2") (pinfunction "2_2") (pintype "passive"))
      (node (ref "U1") (pin "33") (pinfunction "ENB_33") (pintype "input"))
    )
    (net (code "60") (name "/SN65_ENC") (class "Default")
      (node (ref "R11") (pin "1") (pinfunction "1_1") (pintype "passive"))
      (node (ref "R19") (pin "2") (pinfunction "2_2") (pintype "passive"))
      (node (ref "U1") (pin "25") (pinfunction "ENC_25") (pintype "input"))
    )
    (net (code "61") (name "/SN65_END") (class "Default")
      (node (ref "R12") (pin "1") (pinfunction "1_1") (pintype "passive"))
      (node (ref "R20") (pin "2") (pinfunction "2_2") (pintype "passive"))
      (node (ref "U1") (pin "22") (pinfunction "END_22") (pintype "input"))
    )
    (net (code "62") (name "/SN75_ENA") (class "Default")
      (node (ref "R13") (pin "1") (pinfunction "1_1") (pintype "passive"))
      (node (ref "R21") (pin "2") (pinfunction "2_2") (pintype "passive"))
      (node (ref "U2") (pin "5") (pinfunction "ENA_5") (pintype "input"))
    )
    (net (code "63") (name "/SN75_ENB") (class "Default")
      (node (ref "R14") (pin "1") (pinfunction "1_1") (pintype "passive"))
      (node (ref "R22") (pin "2") (pinfunction "2_2") (pintype "passive"))
      (node (ref "U2") (pin "10") (pinfunction "ENB_10") (pintype "input"))
    )
    (net (code "64") (name "/SN75_ENC") (class "Default")
      (node (ref "R15") (pin "1") (pinfunction "1_1") (pintype "passive"))
      (node (ref "R23") (pin "2") (pinfunction "2_2") (pintype "passive"))
      (node (ref "U2") (pin "23") (pinfunction "ENC_23") (pintype "input"))
    )
    (net (code "65") (name "/SN75_END") (class "Default")
      (node (ref "R16") (pin "1") (pinfunction "1_1") (pintype "passive"))
      (node (ref "R24") (pin "2") (pinfunction "2_2") (pintype "passive"))
      (node (ref "U2") (pin "28") (pinfunction "END_28") (pintype "input"))
    )
    (net (code "66") (name "/SPI_CS") (class "Default")
      (node (ref "J4") (pin "11") (pinfunction "11_11") (pintype "passive"))
      (node (ref "U2") (pin "26") (pinfunction "D3A_26") (pintype "input"))
    )
    (net (code "67") (name "/SPI_CS_N") (class "Default")
      (node (ref "P6") (pin "2") (pinfunction "2_2") (pintype "passive"))
      (node (ref "U2") (pin "35") (pinfunction "D3Z_35") (pintype "output"))
    )
    (net (code "68") (name "/SPI_CS_P") (class "Default")
      (node (ref "P6") (pin "1") (pinfunction "1_1") (pintype "passive"))
      (node (ref "U2") (pin "36") (pinfunction "D3Y_36") (pintype "output"))
    )
    (net (code "69") (name "/SPI_MISO") (class "Default")
      (node (ref "J2") (pin "24") (pinfunction "24_24") (pintype "passive"))
      (node (ref "U1") (pin "31") (pinfunction "B2Y_31") (pintype "output"))
    )
    (net (code "70") (name "/SPI_MISO_N") (class "Default")
      (node (ref "P6") (pin "8") (pinfunction "8_8") (pintype "passive"))
      (node (ref "R4") (pin "1") (pinfunction "1_1") (pintype "passive"))
      (node (ref "U1") (pin "9") (pinfunction "B2B_9") (pintype "input"))
    )
    (net (code "71") (name "/SPI_MISO_P") (class "Default")
      (node (ref "P6") (pin "7") (pinfunction "7_7") (pintype "passive"))
      (node (ref "R4") (pin "2") (pinfunction "2_2") (pintype "passive"))
      (node (ref "U1") (pin "8") (pinfunction "B2A_8") (pintype "input"))
    )
    (net (code "72") (name "/SPI_MOSI") (class "Default")
      (node (ref "J2") (pin "28") (pinfunction "28_28") (pintype "passive"))
      (node (ref "U2") (pin "24") (pinfunction "D1A_24") (pintype "input"))
    )
    (net (code "73") (name "/SPI_MOSI_N") (class "Default")
      (node (ref "P6") (pin "6") (pinfunction "6_6") (pintype "passive"))
      (node (ref "U2") (pin "39") (pinfunction "D1Z_39") (pintype "output"))
    )
    (net (code "74") (name "/SPI_MOSI_P") (class "Default")
      (node (ref "P6") (pin "5") (pinfunction "5_5") (pintype "passive"))
      (node (ref "U2") (pin "40") (pinfunction "D1Y_40") (pintype "output"))
    )
    (net (code "75") (name "/SPI_SCLK") (class "Default")
      (node (ref "J2") (pin "26") (pinfunction "26_26") (pintype "passive"))
      (node (ref "U2") (pin "25") (pinfunction "D2A_25") (pintype "input"))
    )
    (net (code "76") (name "/SPI_SCLK_N") (class "Default")
      (node (ref "P6") (pin "4") (pinfunction "4_4") (pintype "passive"))
      (node (ref "U2") (pin "37") (pinfunction "D2Z_37") (pintype "output"))
    )
    (net (code "77") (name "/SPI_SCLK_P") (class "Default")
      (node (ref "P6") (pin "3") (pinfunction "3_3") (pintype "passive"))
      (node (ref "U2") (pin "38") (pinfunction "D2Y_38") (pintype "output"))
    )
    (net (code "78") (name "/TRAN_1") (class "Default")
      (node (ref "P8") (pin "4") (pinfunction "4_4") (pintype "passive"))
      (node (ref "U2") (pin "27") (pinfunction "D4A_27") (pintype "input"))
    )
    (net (code "79") (name "/TRAN_1_N") (class "Default")
      (node (ref "P7") (pin "8") (pinfunction "8_8") (pintype "passive"))
      (node (ref "U2") (pin "33") (pinfunction "D4Z_33") (pintype "output"))
    )
    (net (code "80") (name "/TRAN_1_P") (class "Default")
      (node (ref "P7") (pin "7") (pinfunction "7_7") (pintype "passive"))
      (node (ref "U2") (pin "34") (pinfunction "D4Y_34") (pintype "output"))
    )
    (net (code "81") (name "GND") (class "Default")
      (node (ref "C1") (pin "2") (pinfunction "2_2") (pintype "passive"))
      (node (ref "C2") (pin "2") (pinfunction "2_2") (pintype "passive"))
      (node (ref "C3") (pin "2") (pinfunction "2_2") (pintype "passive"))
      (node (ref "C4") (pin "2") (pinfunction "2_2") (pintype "passive"))
      (node (ref "P5") (pin "3") (pinfunction "3_3") (pintype "passive"))
      (node (ref "P9") (pin "2") (pinfunction "2_2") (pintype "passive"))
      (node (ref "R17") (pin "1") (pinfunction "1_1") (pintype "passive"))
      (node (ref "R18") (pin "1") (pinfunction "1_1") (pintype "passive"))
      (node (ref "R19") (pin "1") (pinfunction "1_1") (pintype "passive"))
      (node (ref "R20") (pin "1") (pinfunction "1_1") (pintype "passive"))
      (node (ref "R21") (pin "1") (pinfunction "1_1") (pintype "passive"))
      (node (ref "R22") (pin "1") (pinfunction "1_1") (pintype "passive"))
      (node (ref "R23") (pin "1") (pinfunction "1_1") (pintype "passive"))
      (node (ref "R24") (pin "1") (pinfunction "1_1") (pintype "passive"))
      (node (ref "U1") (pin "10") (pinfunction "AGND_10") (pintype "power_in"))
      (node (ref "U1") (pin "15") (pinfunction "AGND_15") (pintype "power_in"))
      (node (ref "U1") (pin "20") (pinfunction "GND_20") (pintype "power_in"))
      (node (ref "U1") (pin "28") (pinfunction "DGND_28") (pintype "power_in"))
      (node (ref "U1") (pin "30") (pinfunction "DGND_30") (pintype "power_in"))
      (node (ref "U1") (pin "38") (pinfunction "GND_38") (pintype "power_in"))
      (node (ref "U1") (pin "5") (pinfunction "AGND_5") (pintype "power_in"))
      (node (ref "U2") (pin "1") (pinfunction "GND_1") (pintype "power_in"))
      (node (ref "U2") (pin "15") (pinfunction "GND_15") (pintype "power_in"))
      (node (ref "U2") (pin "18") (pinfunction "GND_18") (pintype "power_in"))
      (node (ref "U2") (pin "29") (pinfunction "GND_29") (pintype "power_in"))
      (node (ref "U2") (pin "32") (pinfunction "GND_32") (pintype "power_in"))
      (node (ref "U2") (pin "4") (pinfunction "GND_4") (pintype "power_in"))
    )
    (net (code "82") (name "VDD") (class "Default")
      (node (ref "C1") (pin "1") (pinfunction "1_1") (pintype "passive"))
      (node (ref "C2") (pin "1") (pinfunction "1_1") (pintype "passive"))
      (node (ref "C3") (pin "1") (pinfunction "1_1") (pintype "passive"))
      (node (ref "C4") (pin "1") (pinfunction "1_1") (pintype "passive"))
      (node (ref "P5") (pin "1") (pinfunction "1_1") (pintype "passive"))
      (node (ref "P9") (pin "1") (pinfunction "1_1") (pintype "passive"))
      (node (ref "R10") (pin "2") (pinfunction "2_2") (pintype "passive"))
      (node (ref "R11") (pin "2") (pinfunction "2_2") (pintype "passive"))
      (node (ref "R12") (pin "2") (pinfunction "2_2") (pintype "passive"))
      (node (ref "R13") (pin "2") (pinfunction "2_2") (pintype "passive"))
      (node (ref "R14") (pin "2") (pinfunction "2_2") (pintype "passive"))
      (node (ref "R15") (pin "2") (pinfunction "2_2") (pintype "passive"))
      (node (ref "R16") (pin "2") (pinfunction "2_2") (pintype "passive"))
      (node (ref "R9") (pin "2") (pinfunction "2_2") (pintype "passive"))
      (node (ref "U1") (pin "21") (pinfunction "VCC_21") (pintype "power_in"))
      (node (ref "U1") (pin "29") (pinfunction "DVCC_29") (pintype "power_in"))
      (node (ref "U1") (pin "37") (pinfunction "VCC_37") (pintype "power_in"))
      (node (ref "U2") (pin "16") (pinfunction "VCC_16") (pintype "power_in"))
      (node (ref "U2") (pin "17") (pinfunction "VCC_17") (pintype "power_in"))
      (node (ref "U2") (pin "2") (pinfunction "VCC_2") (pintype "power_in"))
      (node (ref "U2") (pin "3") (pinfunction "VCC_3") (pintype "power_in"))
      (node (ref "U2") (pin "30") (pinfunction "VCC_30") (pintype "power_in"))
      (node (ref "U2") (pin "31") (pinfunction "VCC_31") (pintype "power_in"))
    )
    (net (code "83") (name "VSTIM+") (class "Default")
      (node (ref "P5") (pin "4") (pinfunction "4_4") (pintype "passive"))
      (node (ref "P9") (pin "3") (pinfunction "3_3") (pintype "passive"))
    )
    (net (code "84") (name "VSTIM-") (class "Default")
      (node (ref "P5") (pin "2") (pinfunction "2_2") (pintype "passive"))
      (node (ref "P9") (pin "4") (pinfunction "4_4") (pintype "passive"))
    )
    (net (code "85") (name "unconnected-(J1-Pad1)") (class "Default")
      (node (ref "J1") (pin "1") (pinfunction "1_1") (pintype "passive+no_connect"))
    )
    (net (code "86") (name "unconnected-(J1-Pad2)") (class "Default")
      (node (ref "J1") (pin "2") (pinfunction "2_2") (pintype "passive+no_connect"))
    )
    (net (code "87") (name "unconnected-(J1-Pad3)") (class "Default")
      (node (ref "J1") (pin "3") (pinfunction "3_3") (pintype "passive+no_connect"))
    )
    (net (code "88") (name "unconnected-(J1-Pad4)") (class "Default")
      (node (ref "J1") (pin "4") (pinfunction "4_4") (pintype "passive+no_connect"))
    )
    (net (code "89") (name "unconnected-(J1-Pad5)") (class "Default")
      (node (ref "J1") (pin "5") (pinfunction "5_5") (pintype "passive+no_connect"))
    )
    (net (code "90") (name "unconnected-(J1-Pad6)") (class "Default")
      (node (ref "J1") (pin "6") (pinfunction "6_6") (pintype "passive+no_connect"))
    )
    (net (code "91") (name "unconnected-(J1-Pad7)") (class "Default")
      (node (ref "J1") (pin "7") (pinfunction "7_7") (pintype "passive+no_connect"))
    )
    (net (code "92") (name "unconnected-(J1-Pad8)") (class "Default")
      (node (ref "J1") (pin "8") (pinfunction "8_8") (pintype "passive+no_connect"))
    )
    (net (code "93") (name "unconnected-(J1-Pad9)") (class "Default")
      (node (ref "J1") (pin "9") (pinfunction "9_9") (pintype "passive+no_connect"))
    )
    (net (code "94") (name "unconnected-(J1-Pad10)") (class "Default")
      (node (ref "J1") (pin "10") (pinfunction "10_10") (pintype "passive+no_connect"))
    )
    (net (code "95") (name "unconnected-(J1-Pad11)") (class "Default")
      (node (ref "J1") (pin "11") (pinfunction "11_11") (pintype "passive+no_connect"))
    )
    (net (code "96") (name "unconnected-(J1-Pad12)") (class "Default")
      (node (ref "J1") (pin "12") (pinfunction "12_12") (pintype "passive+no_connect"))
    )
    (net (code "97") (name "unconnected-(J1-Pad13)") (class "Default")
      (node (ref "J1") (pin "13") (pinfunction "13_13") (pintype "passive+no_connect"))
    )
    (net (code "98") (name "unconnected-(J1-Pad14)") (class "Default")
      (node (ref "J1") (pin "14") (pinfunction "14_14") (pintype "passive+no_connect"))
    )
    (net (code "99") (name "unconnected-(J1-Pad15)") (class "Default")
      (node (ref "J1") (pin "15") (pinfunction "15_15") (pintype "passive+no_connect"))
    )
    (net (code "100") (name "unconnected-(J1-Pad16)") (class "Default")
      (node (ref "J1") (pin "16") (pinfunction "16_16") (pintype "passive+no_connect"))
    )
    (net (code "101") (name "unconnected-(J2-Pad1)") (class "Default")
      (node (ref "J2") (pin "1") (pinfunction "1_1") (pintype "passive+no_connect"))
    )
    (net (code "102") (name "unconnected-(J2-Pad2)") (class "Default")
      (node (ref "J2") (pin "2") (pinfunction "2_2") (pintype "passive+no_connect"))
    )
    (net (code "103") (name "unconnected-(J2-Pad3)") (class "Default")
      (node (ref "J2") (pin "3") (pinfunction "3_3") (pintype "passive+no_connect"))
    )
    (net (code "104") (name "unconnected-(J2-Pad4)") (class "Default")
      (node (ref "J2") (pin "4") (pinfunction "4_4") (pintype "passive+no_connect"))
    )
    (net (code "105") (name "unconnected-(J2-Pad5)") (class "Default")
      (node (ref "J2") (pin "5") (pinfunction "5_5") (pintype "passive+no_connect"))
    )
    (net (code "106") (name "unconnected-(J2-Pad6)") (class "Default")
      (node (ref "J2") (pin "6") (pinfunction "6_6") (pintype "passive+no_connect"))
    )
    (net (code "107") (name "unconnected-(J2-Pad7)") (class "Default")
      (node (ref "J2") (pin "7") (pinfunction "7_7") (pintype "passive+no_connect"))
    )
    (net (code "108") (name "unconnected-(J2-Pad8)") (class "Default")
      (node (ref "J2") (pin "8") (pinfunction "8_8") (pintype "passive+no_connect"))
    )
    (net (code "109") (name "unconnected-(J2-Pad10)") (class "Default")
      (node (ref "J2") (pin "10") (pinfunction "10_10") (pintype "passive+no_connect"))
    )
    (net (code "110") (name "unconnected-(J2-Pad11)") (class "Default")
      (node (ref "J2") (pin "11") (pinfunction "11_11") (pintype "passive+no_connect"))
    )
    (net (code "111") (name "unconnected-(J2-Pad12)") (class "Default")
      (node (ref "J2") (pin "12") (pinfunction "12_12") (pintype "passive+no_connect"))
    )
    (net (code "112") (name "unconnected-(J2-Pad13)") (class "Default")
      (node (ref "J2") (pin "13") (pinfunction "13_13") (pintype "passive+no_connect"))
    )
    (net (code "113") (name "unconnected-(J2-Pad14)") (class "Default")
      (node (ref "J2") (pin "14") (pinfunction "14_14") (pintype "passive+no_connect"))
    )
    (net (code "114") (name "unconnected-(J2-Pad15)") (class "Default")
      (node (ref "J2") (pin "15") (pinfunction "15_15") (pintype "passive+no_connect"))
    )
    (net (code "115") (name "unconnected-(J2-Pad16)") (class "Default")
      (node (ref "J2") (pin "16") (pinfunction "16_16") (pintype "passive+no_connect"))
    )
    (net (code "116") (name "unconnected-(J2-Pad17)") (class "Default")
      (node (ref "J2") (pin "17") (pinfunction "17_17") (pintype "passive+no_connect"))
    )
    (net (code "117") (name "unconnected-(J2-Pad18)") (class "Default")
      (node (ref "J2") (pin "18") (pinfunction "18_18") (pintype "passive+no_connect"))
    )
    (net (code "118") (name "unconnected-(J2-Pad19)") (class "Default")
      (node (ref "J2") (pin "19") (pinfunction "19_19") (pintype "passive+no_connect"))
    )
    (net (code "119") (name "unconnected-(J2-Pad20)") (class "Default")
      (node (ref "J2") (pin "20") (pinfunction "20_20") (pintype "passive+no_connect"))
    )
    (net (code "120") (name "unconnected-(J2-Pad21)") (class "Default")
      (node (ref "J2") (pin "21") (pinfunction "21_21") (pintype "passive+no_connect"))
    )
    (net (code "121") (name "unconnected-(J2-Pad22)") (class "Default")
      (node (ref "J2") (pin "22") (pinfunction "22_22") (pintype "passive+no_connect"))
    )
    (net (code "122") (name "unconnected-(J2-Pad23)") (class "Default")
      (node (ref "J2") (pin "23") (pinfunction "23_23") (pintype "passive+no_connect"))
    )
    (net (code "123") (name "unconnected-(J2-Pad25)") (class "Default")
      (node (ref "J2") (pin "25") (pinfunction "25_25") (pintype "passive+no_connect"))
    )
    (net (code "124") (name "unconnected-(J2-Pad27)") (class "Default")
      (node (ref "J2") (pin "27") (pinfunction "27_27") (pintype "passive+no_connect"))
    )
    (net (code "125") (name "unconnected-(J2-Pad29)") (class "Default")
      (node (ref "J2") (pin "29") (pinfunction "29_29") (pintype "passive+no_connect"))
    )
    (net (code "126") (name "unconnected-(J2-Pad30)") (class "Default")
      (node (ref "J2") (pin "30") (pinfunction "30_30") (pintype "passive+no_connect"))
    )
    (net (code "127") (name "unconnected-(J3-Pad1)") (class "Default")
      (node (ref "J3") (pin "1") (pinfunction "1_1") (pintype "passive+no_connect"))
    )
    (net (code "128") (name "unconnected-(J3-Pad2)") (class "Default")
      (node (ref "J3") (pin "2") (pinfunction "2_2") (pintype "passive+no_connect"))
    )
    (net (code "129") (name "unconnected-(J3-Pad4)") (class "Default")
      (node (ref "J3") (pin "4") (pinfunction "4_4") (pintype "passive+no_connect"))
    )
    (net (code "130") (name "unconnected-(J3-Pad6)") (class "Default")
      (node (ref "J3") (pin "6") (pinfunction "6_6") (pintype "passive+no_connect"))
    )
    (net (code "131") (name "unconnected-(J3-Pad8)") (class "Default")
      (node (ref "J3") (pin "8") (pinfunction "8_8") (pintype "passive+no_connect"))
    )
    (net (code "132") (name "unconnected-(J3-Pad11)") (class "Default")
      (node (ref "J3") (pin "11") (pinfunction "11_11") (pintype "passive+no_connect"))
    )
    (net (code "133") (name "unconnected-(J3-Pad16)") (class "Default")
      (node (ref "J3") (pin "16") (pinfunction "16_16") (pintype "passive+no_connect"))
    )
    (net (code "134") (name "unconnected-(J3-Pad18)") (class "Default")
      (node (ref "J3") (pin "18") (pinfunction "18_18") (pintype "passive+no_connect"))
    )
    (net (code "135") (name "unconnected-(J3-Pad20)") (class "Default")
      (node (ref "J3") (pin "20") (pinfunction "20_20") (pintype "passive+no_connect"))
    )
    (net (code "136") (name "unconnected-(J4-Pad1)") (class "Default")
      (node (ref "J4") (pin "1") (pinfunction "1_1") (pintype "passive+no_connect"))
    )
    (net (code "137") (name "unconnected-(J4-Pad2)") (class "Default")
      (node (ref "J4") (pin "2") (pinfunction "2_2") (pintype "passive+no_connect"))
    )
    (net (code "138") (name "unconnected-(J4-Pad3)") (class "Default")
      (node (ref "J4") (pin "3") (pinfunction "3_3") (pintype "passive+no_connect"))
    )
    (net (code "139") (name "unconnected-(J4-Pad4)") (class "Default")
      (node (ref "J4") (pin "4") (pinfunction "4_4") (pintype "passive+no_connect"))
    )
    (net (code "140") (name "unconnected-(J4-Pad5)") (class "Default")
      (node (ref "J4") (pin "5") (pinfunction "5_5") (pintype "passive+no_connect"))
    )
    (net (code "141") (name "unconnected-(J4-Pad7)") (class "Default")
      (node (ref "J4") (pin "7") (pinfunction "7_7") (pintype "passive+no_connect"))
    )
    (net (code "142") (name "unconnected-(J4-Pad9)") (class "Default")
      (node (ref "J4") (pin "9") (pinfunction "9_9") (pintype "passive+no_connect"))
    )
    (net (code "143") (name "unconnected-(J4-Pad12)") (class "Default")
      (node (ref "J4") (pin "12") (pinfunction "12_12") (pintype "passive+no_connect"))
    )
    (net (code "144") (name "unconnected-(J4-Pad13)") (class "Default")
      (node (ref "J4") (pin "13") (pinfunction "13_13") (pintype "passive+no_connect"))
    )
    (net (code "145") (name "unconnected-(J4-Pad14)") (class "Default")
      (node (ref "J4") (pin "14") (pinfunction "14_14") (pintype "passive+no_connect"))
    )
    (net (code "146") (name "unconnected-(J4-Pad15)") (class "Default")
      (node (ref "J4") (pin "15") (pinfunction "15_15") (pintype "passive+no_connect"))
    )
    (net (code "147") (name "unconnected-(J4-Pad16)") (class "Default")
      (node (ref "J4") (pin "16") (pinfunction "16_16") (pintype "passive+no_connect"))
    )
    (net (code "148") (name "unconnected-(J4-Pad17)") (class "Default")
      (node (ref "J4") (pin "17") (pinfunction "17_17") (pintype "passive+no_connect"))
    )
    (net (code "149") (name "unconnected-(J4-Pad18)") (class "Default")
      (node (ref "J4") (pin "18") (pinfunction "18_18") (pintype "passive+no_connect"))
    )
    (net (code "150") (name "unconnected-(J4-Pad19)") (class "Default")
      (node (ref "J4") (pin "19") (pinfunction "19_19") (pintype "passive+no_connect"))
    )
    (net (code "151") (name "unconnected-(J4-Pad20)") (class "Default")
      (node (ref "J4") (pin "20") (pinfunction "20_20") (pintype "passive+no_connect"))
    )
    (net (code "152") (name "unconnected-(J4-Pad21)") (class "Default")
      (node (ref "J4") (pin "21") (pinfunction "21_21") (pintype "passive+no_connect"))
    )
    (net (code "153") (name "unconnected-(J4-Pad22)") (class "Default")
      (node (ref "J4") (pin "22") (pinfunction "22_22") (pintype "passive+no_connect"))
    )
    (net (code "154") (name "unconnected-(J4-Pad23)") (class "Default")
      (node (ref "J4") (pin "23") (pinfunction "23_23") (pintype "passive+no_connect"))
    )
    (net (code "155") (name "unconnected-(J4-Pad24)") (class "Default")
      (node (ref "J4") (pin "24") (pinfunction "24_24") (pintype "passive+no_connect"))
    )
    (net (code "156") (name "unconnected-(J4-Pad25)") (class "Default")
      (node (ref "J4") (pin "25") (pinfunction "25_25") (pintype "passive+no_connect"))
    )
    (net (code "157") (name "unconnected-(J4-Pad27)") (class "Default")
      (node (ref "J4") (pin "27") (pinfunction "27_27") (pintype "passive+no_connect"))
    )
    (net (code "158") (name "unconnected-(J4-Pad28)") (class "Default")
      (node (ref "J4") (pin "28") (pinfunction "28_28") (pintype "passive+no_connect"))
    )
    (net (code "159") (name "unconnected-(J4-Pad29)") (class "Default")
      (node (ref "J4") (pin "29") (pinfunction "29_29") (pintype "passive+no_connect"))
    )
    (net (code "160") (name "unconnected-(J4-Pad30)") (class "Default")
      (node (ref "J4") (pin "30") (pinfunction "30_30") (pintype "passive+no_connect"))
    )
    (net (code "161") (name "unconnected-(J4-Pad31)") (class "Default")
      (node (ref "J4") (pin "31") (pinfunction "31_31") (pintype "passive+no_connect"))
    )
    (net (code "162") (name "unconnected-(J4-Pad32)") (class "Default")
      (node (ref "J4") (pin "32") (pinfunction "32_32") (pintype "passive+no_connect"))
    )
    (net (code "163") (name "unconnected-(J4-Pad33)") (class "Default")
      (node (ref "J4") (pin "33") (pinfunction "33_33") (pintype "passive+no_connect"))
    )
    (net (code "164") (name "unconnected-(J4-Pad34)") (class "Default")
      (node (ref "J4") (pin "34") (pinfunction "34_34") (pintype "passive+no_connect"))
    )
  )
)
